# ftdi-basic-switchable.net
KiCad netlist of a schematic drawn in EAGLE
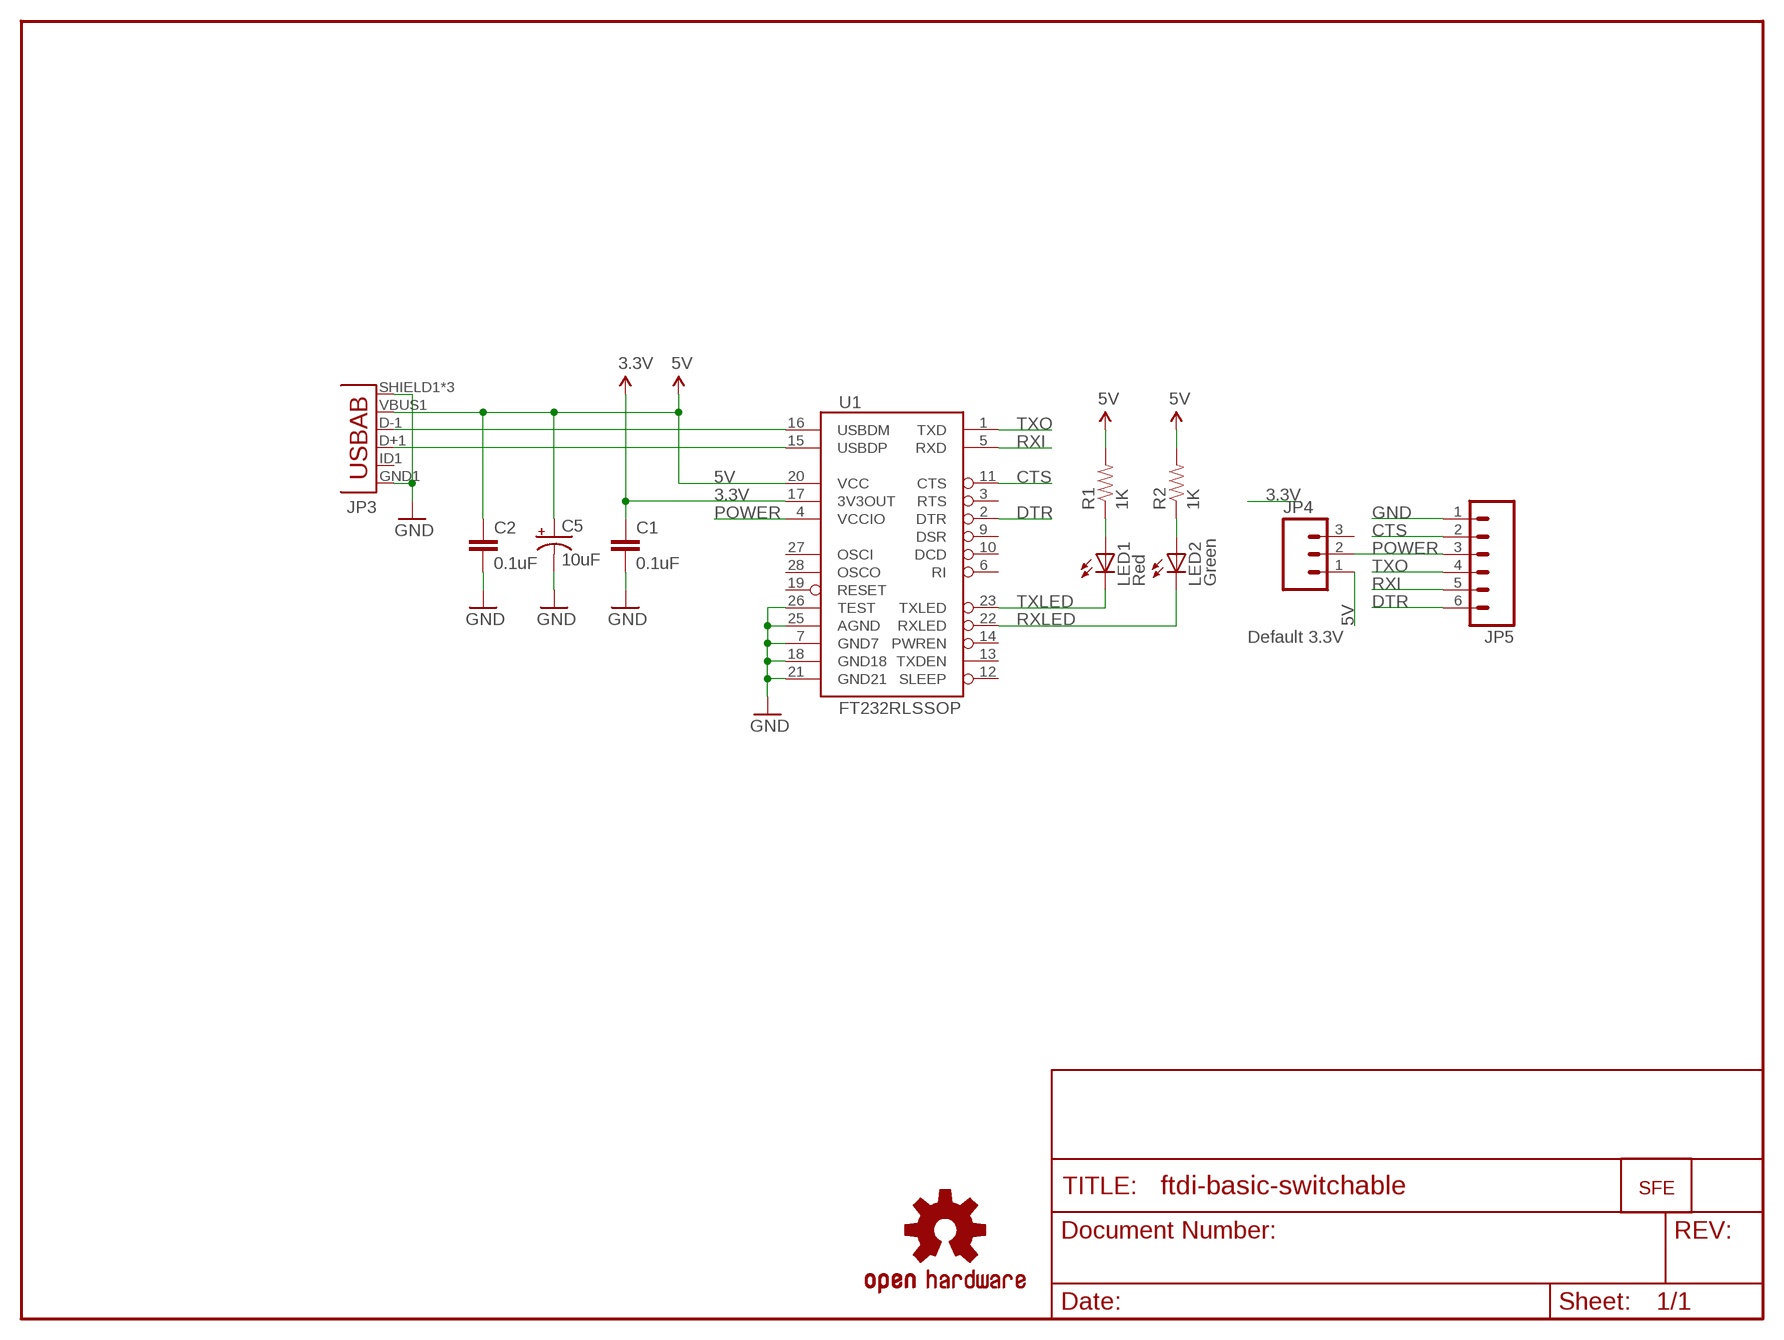
[diagram p0: schematic, sheet 1]

(export (version "E")
  (design (tool "Eeschema 10.0.6"))
  (components
    (comp (ref "C1")
      (value "0.1uF")
      (footprint "eagle-import:0402-CAP")
      (libsource (lib "eagle-import") (part "CAP0402-CAP"))
    )
    (comp (ref "C2")
      (value "0.1uF")
      (footprint "eagle-import:0402-CAP")
      (libsource (lib "eagle-import") (part "CAP0402-CAP"))
    )
    (comp (ref "C5")
      (value "10uF")
      (footprint "eagle-import:EIA3216")
      (libsource (lib "eagle-import") (part "CAP_POL1206"))
    )
    (comp (ref "JP2")
      (value "LOGO-SFESK")
      (footprint "eagle-import:SFE-LOGO-FLAME")
      (libsource (lib "eagle-import") (part "LOGO-SFESK"))
    )
    (comp (ref "JP3")
      (value "USB-ABCONN-11794")
      (footprint "eagle-import:USB-AB-MICRO-SMD_V03")
      (libsource (lib "eagle-import") (part "USB-ABCONN-11794"))
    )
    (comp (ref "JP4")
      (value "M03SMD_RA_MALE")
      (footprint "eagle-import:1X03_SMD_RA_MALE")
      (libsource (lib "eagle-import") (part "M03SMD_RA_MALE"))
    )
    (comp (ref "JP5")
      (value "M06SMD-FEMALE-V2-NOSILK")
      (footprint "eagle-import:1X06-SMD-FEMALE-V2-NOSILK")
      (libsource (lib "eagle-import") (part "M06SMD-FEMALE-V2-NOSILK"))
    )
    (comp (ref "LED1")
      (value "Red")
      (footprint "eagle-import:LED-0603")
      (libsource (lib "eagle-import") (part "LED0603"))
    )
    (comp (ref "LED2")
      (value "Green")
      (footprint "eagle-import:LED-0603")
      (libsource (lib "eagle-import") (part "LED0603"))
    )
    (comp (ref "LOGO1")
      (value "OSHW-LOGOS")
      (footprint "eagle-import:OSHW-LOGO-S")
      (libsource (lib "eagle-import") (part "OSHW-LOGOS"))
    )
    (comp (ref "R1")
      (value "1K")
      (footprint "eagle-import:0402-RES")
      (libsource (lib "eagle-import") (part "RESISTOR0402-RES"))
    )
    (comp (ref "R2")
      (value "1K")
      (footprint "eagle-import:0402-RES")
      (libsource (lib "eagle-import") (part "RESISTOR0402-RES"))
    )
    (comp (ref "U1")
      (value "FT232RLSSOP")
      (footprint "eagle-import:SSOP28DB")
      (libsource (lib "eagle-import") (part "FT232RLSSOP"))
    )
  )
  (nets
    (net (code "1") (name "/CTS") (class "Default")
      (node (ref "JP5") (pin "2") (pinfunction "2_2") (pintype "passive"))
      (node (ref "U1") (pin "11") (pinfunction "CTS_11") (pintype "input"))
    )
    (net (code "2") (name "/DTR") (class "Default")
      (node (ref "JP5") (pin "6") (pinfunction "6_6") (pintype "passive"))
      (node (ref "U1") (pin "2") (pinfunction "DTR_2") (pintype "output"))
    )
    (net (code "3") (name "/POWER") (class "Default")
      (node (ref "JP4") (pin "2") (pinfunction "2_2") (pintype "passive"))
      (node (ref "JP5") (pin "3") (pinfunction "3_3") (pintype "passive"))
      (node (ref "U1") (pin "4") (pinfunction "VCCIO_4") (pintype "power_in"))
    )
    (net (code "4") (name "/RXI") (class "Default")
      (node (ref "JP5") (pin "5") (pinfunction "5_5") (pintype "passive"))
      (node (ref "U1") (pin "5") (pinfunction "RXD_5") (pintype "input"))
    )
    (net (code "5") (name "/RXLED") (class "Default")
      (node (ref "LED2") (pin "C") (pinfunction "C_C") (pintype "passive"))
      (node (ref "U1") (pin "22") (pinfunction "RXLED_22") (pintype "input"))
    )
    (net (code "6") (name "/TXLED") (class "Default")
      (node (ref "LED1") (pin "C") (pinfunction "C_C") (pintype "passive"))
      (node (ref "U1") (pin "23") (pinfunction "TXLED_23") (pintype "input"))
    )
    (net (code "7") (name "/TXO") (class "Default")
      (node (ref "JP5") (pin "4") (pinfunction "4_4") (pintype "passive"))
      (node (ref "U1") (pin "1") (pinfunction "TXD_1") (pintype "output"))
    )
    (net (code "8") (name "3.3V") (class "Default")
      (node (ref "C1") (pin "1") (pinfunction "1_1") (pintype "passive"))
      (node (ref "U1") (pin "17") (pinfunction "3V3OUT_17") (pintype "output"))
    )
    (net (code "9") (name "5V") (class "Default")
      (node (ref "C2") (pin "1") (pinfunction "1_1") (pintype "passive"))
      (node (ref "C5") (pin "A") (pinfunction "+_A") (pintype "passive"))
      (node (ref "JP3") (pin "VBUS1") (pinfunction "VBUS_VBUS1") (pintype "bidirectional"))
      (node (ref "JP4") (pin "1") (pinfunction "1_1") (pintype "passive"))
      (node (ref "R1") (pin "2") (pinfunction "2_2") (pintype "passive"))
      (node (ref "R2") (pin "2") (pinfunction "2_2") (pintype "passive"))
      (node (ref "U1") (pin "20") (pinfunction "VCC_20") (pintype "power_in"))
    )
    (net (code "10") (name "GND") (class "Default")
      (node (ref "C1") (pin "2") (pinfunction "2_2") (pintype "passive"))
      (node (ref "C2") (pin "2") (pinfunction "2_2") (pintype "passive"))
      (node (ref "C5") (pin "C") (pinfunction "-_C") (pintype "passive"))
      (node (ref "JP3") (pin "GND1") (pinfunction "GND_GND1") (pintype "bidirectional"))
      (node (ref "JP3") (pin "SHIELD1") (pinfunction "SHIELD_SHIELD1") (pintype "bidirectional"))
      (node (ref "JP3") (pin "SHIELD2") (pinfunction "SHIELD_SHIELD2") (pintype "bidirectional"))
      (node (ref "JP3") (pin "SHIELD3") (pinfunction "SHIELD_SHIELD3") (pintype "bidirectional"))
      (node (ref "JP5") (pin "1") (pinfunction "1_1") (pintype "passive"))
      (node (ref "U1") (pin "18") (pinfunction "GND18_18") (pintype "power_in"))
      (node (ref "U1") (pin "21") (pinfunction "GND21_21") (pintype "power_in"))
      (node (ref "U1") (pin "25") (pinfunction "AGND_25") (pintype "power_in"))
      (node (ref "U1") (pin "26") (pinfunction "TEST_26") (pintype "input"))
      (node (ref "U1") (pin "7") (pinfunction "GND7_7") (pintype "power_in"))
    )
    (net (code "11") (name "Net-(JP3-D+)") (class "Default")
      (node (ref "JP3") (pin "D+1") (pinfunction "D+_D+1") (pintype "bidirectional"))
      (node (ref "U1") (pin "15") (pinfunction "USBDP_15") (pintype "bidirectional"))
    )
    (net (code "12") (name "Net-(JP3-D-)") (class "Default")
      (node (ref "JP3") (pin "D-1") (pinfunction "D-_D-1") (pintype "bidirectional"))
      (node (ref "U1") (pin "16") (pinfunction "USBDM_16") (pintype "bidirectional"))
    )
    (net (code "13") (name "Net-(LED1-PadA)") (class "Default")
      (node (ref "LED1") (pin "A") (pinfunction "A_A") (pintype "passive"))
      (node (ref "R1") (pin "1") (pinfunction "1_1") (pintype "passive"))
    )
    (net (code "14") (name "Net-(LED2-PadA)") (class "Default")
      (node (ref "LED2") (pin "A") (pinfunction "A_A") (pintype "passive"))
      (node (ref "R2") (pin "1") (pinfunction "1_1") (pintype "passive"))
    )
    (net (code "15") (name "unconnected-(JP3-USBID-PadID1)") (class "Default")
      (node (ref "JP3") (pin "ID1") (pinfunction "USBID_ID1") (pintype "bidirectional"))
    )
    (net (code "16") (name "unconnected-(JP4-Pad3)") (class "Default")
      (node (ref "JP4") (pin "3") (pinfunction "3_3") (pintype "passive"))
    )
    (net (code "17") (name "unconnected-(U1-DCD-Pad10)") (class "Default")
      (node (ref "U1") (pin "10") (pinfunction "DCD_10") (pintype "input"))
    )
    (net (code "18") (name "unconnected-(U1-DSR-Pad9)") (class "Default")
      (node (ref "U1") (pin "9") (pinfunction "DSR_9") (pintype "input"))
    )
    (net (code "19") (name "unconnected-(U1-OSCI-Pad27)") (class "Default")
      (node (ref "U1") (pin "27") (pinfunction "OSCI_27") (pintype "input"))
    )
    (net (code "20") (name "unconnected-(U1-OSCO-Pad28)") (class "Default")
      (node (ref "U1") (pin "28") (pinfunction "OSCO_28") (pintype "output"))
    )
    (net (code "21") (name "unconnected-(U1-PWREN-Pad14)") (class "Default")
      (node (ref "U1") (pin "14") (pinfunction "PWREN_14") (pintype "input"))
    )
    (net (code "22") (name "unconnected-(U1-RESET-Pad19)") (class "Default")
      (node (ref "U1") (pin "19") (pinfunction "RESET_19") (pintype "input"))
    )
    (net (code "23") (name "unconnected-(U1-RI-Pad6)") (class "Default")
      (node (ref "U1") (pin "6") (pinfunction "RI_6") (pintype "input"))
    )
    (net (code "24") (name "unconnected-(U1-RTS-Pad3)") (class "Default")
      (node (ref "U1") (pin "3") (pinfunction "RTS_3") (pintype "output"))
    )
    (net (code "25") (name "unconnected-(U1-SLEEP-Pad12)") (class "Default")
      (node (ref "U1") (pin "12") (pinfunction "SLEEP_12") (pintype "input"))
    )
    (net (code "26") (name "unconnected-(U1-TXDEN-Pad13)") (class "Default")
      (node (ref "U1") (pin "13") (pinfunction "TXDEN_13") (pintype "input"))
    )
  )
)
